# Wiring_Harness_Validator_MX150L_Rev1.net
KiCad netlist of a schematic drawn in EAGLE
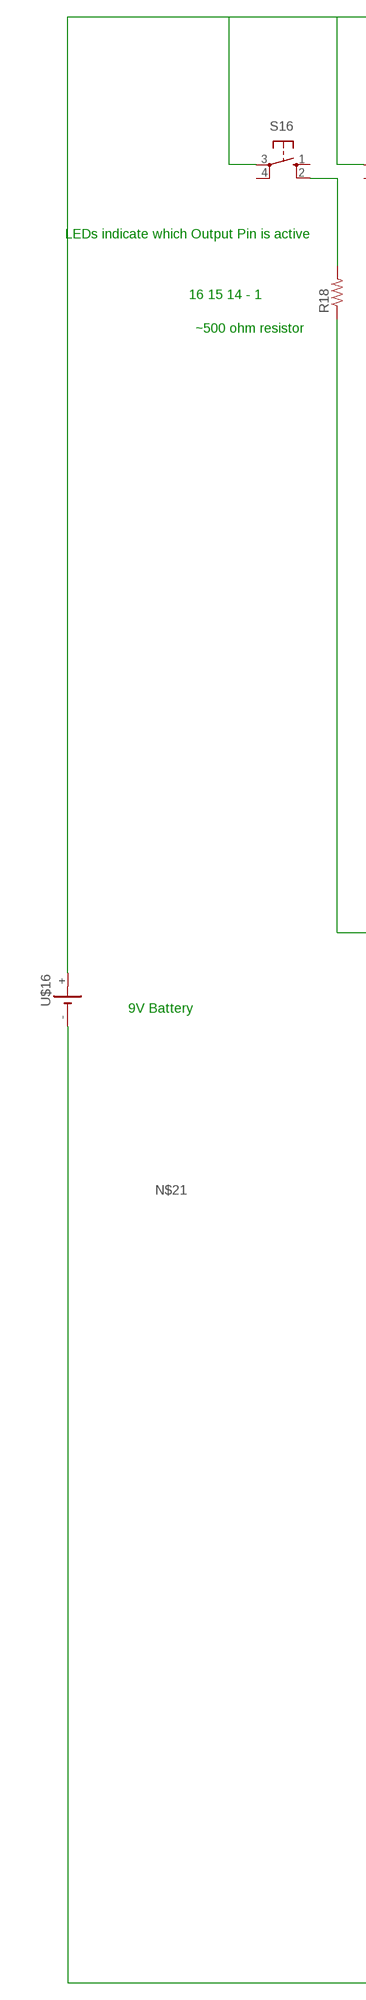
[diagram p0: schematic, sheet 1, part 1 of 2]
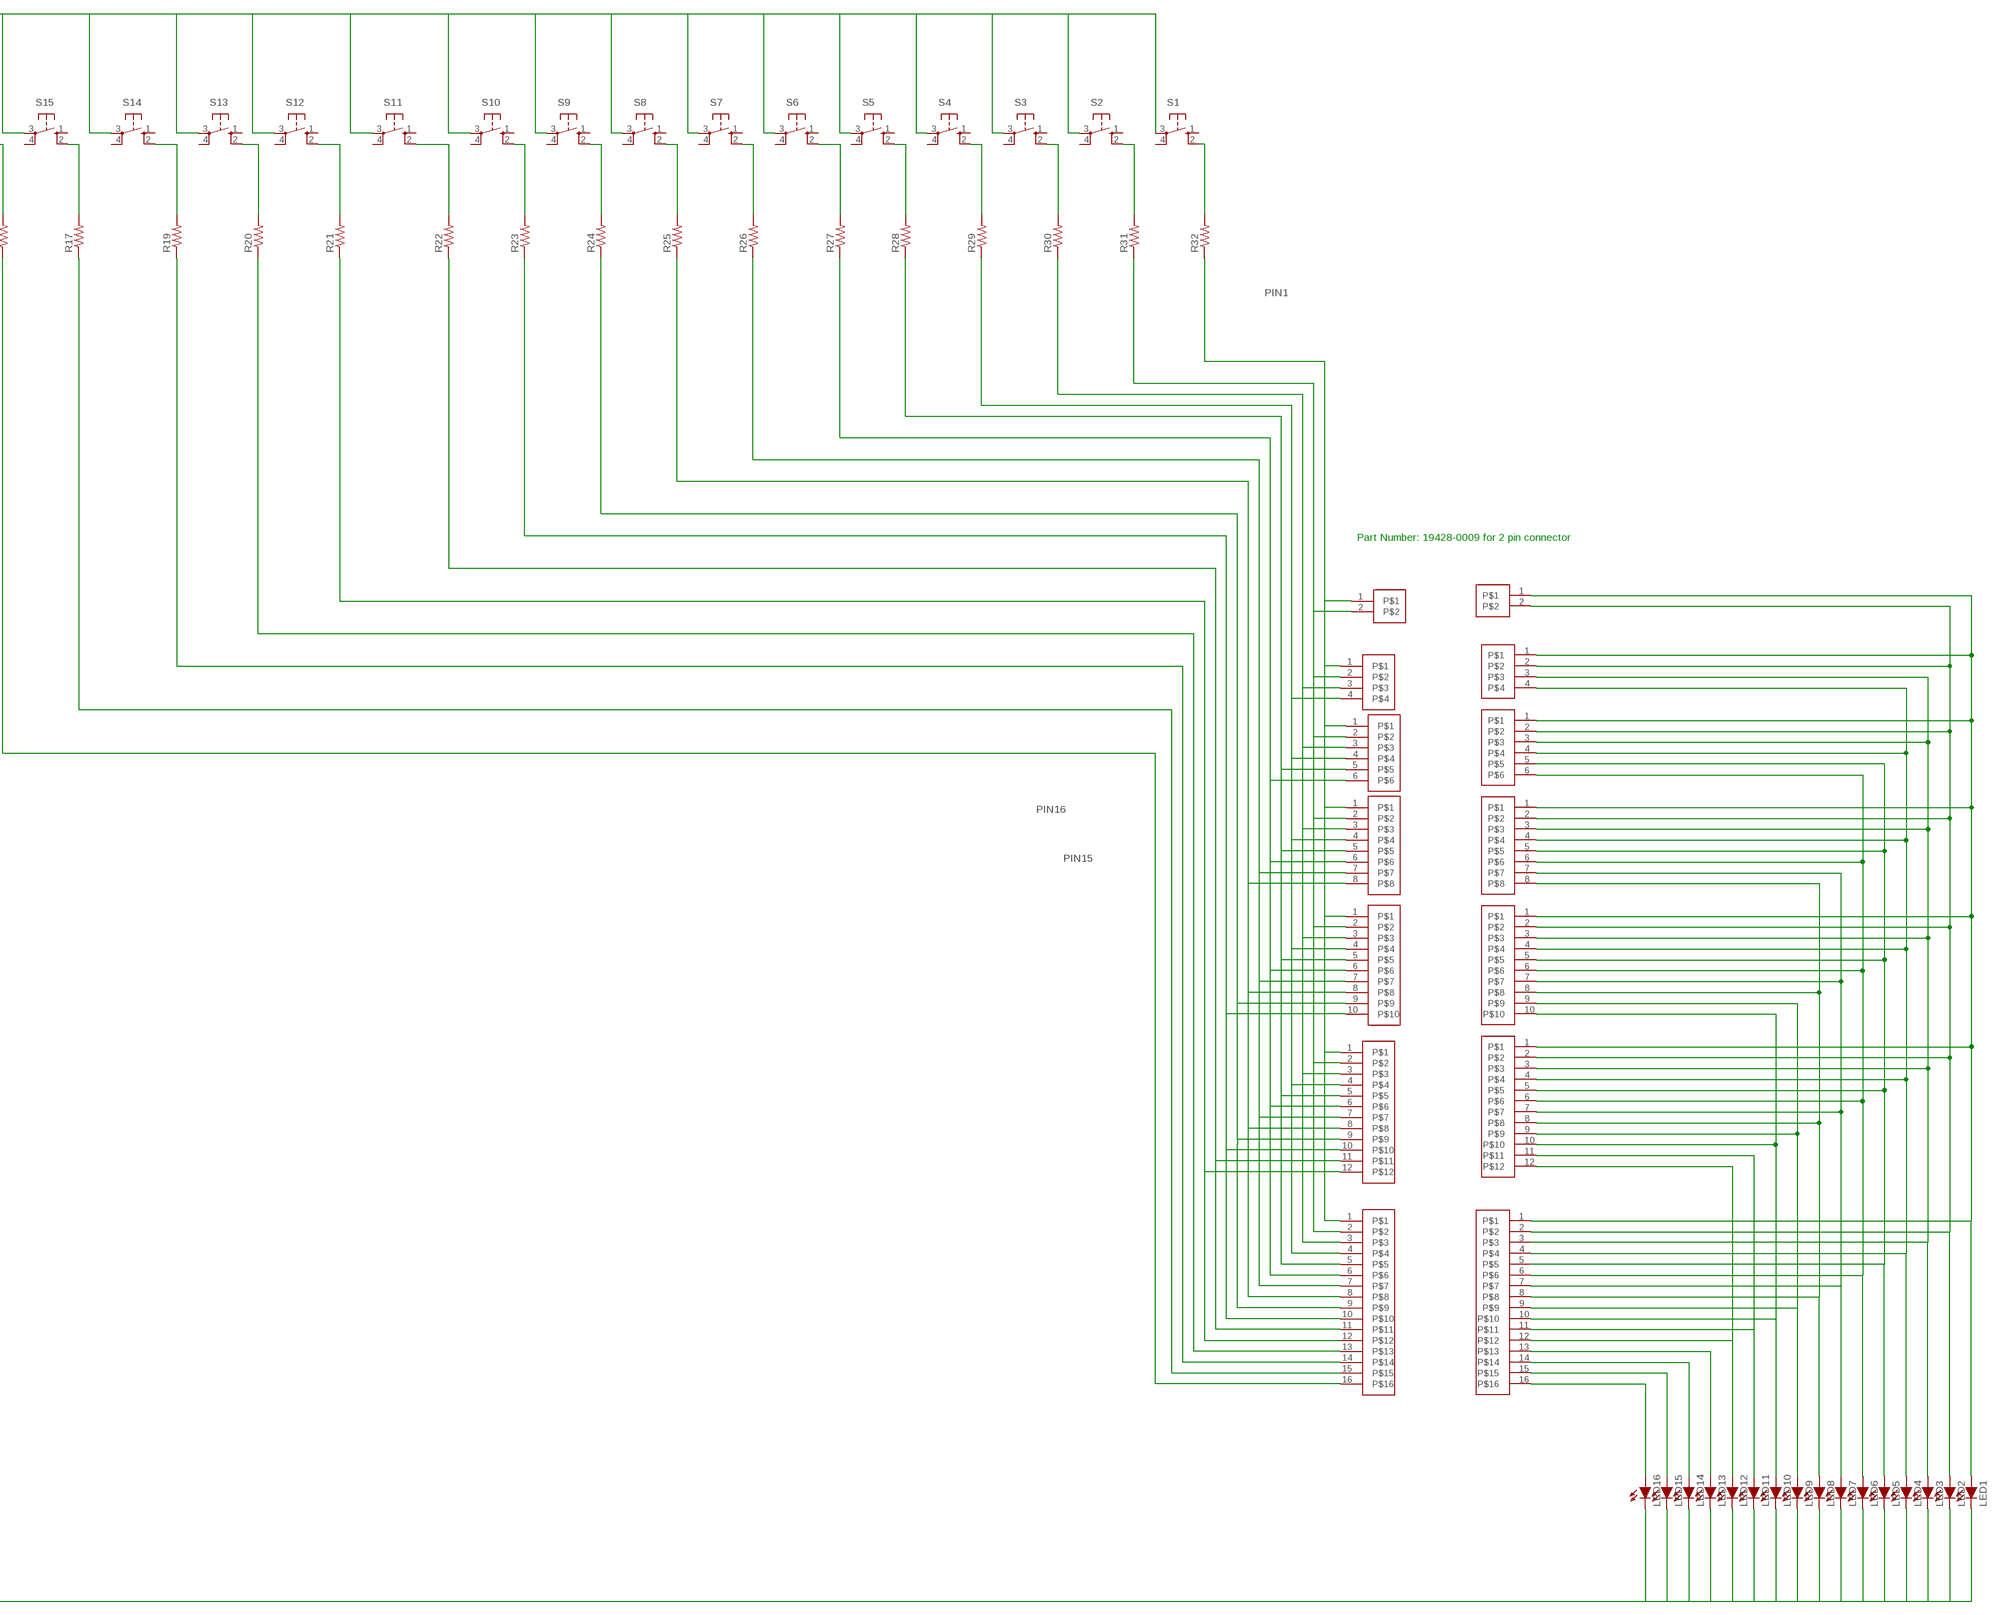
[diagram p1: schematic, sheet 1, part 2 of 2]

(export (version "E")
  (design (tool "Eeschema 10.0.6"))
  (components
    (comp (ref "LED1")
      (value "LED-5MM")
      (footprint "eagle-import:LED-5MM")
      (libsource (lib "eagle-import") (part "LED-5MM"))
    )
    (comp (ref "LED2")
      (value "LED-5MM")
      (footprint "eagle-import:LED-5MM")
      (libsource (lib "eagle-import") (part "LED-5MM"))
    )
    (comp (ref "LED3")
      (value "LED-5MM")
      (footprint "eagle-import:LED-5MM")
      (libsource (lib "eagle-import") (part "LED-5MM"))
    )
    (comp (ref "LED4")
      (value "LED-5MM")
      (footprint "eagle-import:LED-5MM")
      (libsource (lib "eagle-import") (part "LED-5MM"))
    )
    (comp (ref "LED5")
      (value "LED-5MM")
      (footprint "eagle-import:LED-5MM")
      (libsource (lib "eagle-import") (part "LED-5MM"))
    )
    (comp (ref "LED6")
      (value "LED-5MM")
      (footprint "eagle-import:LED-5MM")
      (libsource (lib "eagle-import") (part "LED-5MM"))
    )
    (comp (ref "LED7")
      (value "LED-5MM")
      (footprint "eagle-import:LED-5MM")
      (libsource (lib "eagle-import") (part "LED-5MM"))
    )
    (comp (ref "LED8")
      (value "LED-5MM")
      (footprint "eagle-import:LED-5MM")
      (libsource (lib "eagle-import") (part "LED-5MM"))
    )
    (comp (ref "LED9")
      (value "LED-5MM")
      (footprint "eagle-import:LED-5MM")
      (libsource (lib "eagle-import") (part "LED-5MM"))
    )
    (comp (ref "LED10")
      (value "LED-5MM")
      (footprint "eagle-import:LED-5MM")
      (libsource (lib "eagle-import") (part "LED-5MM"))
    )
    (comp (ref "LED11")
      (value "LED-5MM")
      (footprint "eagle-import:LED-5MM")
      (libsource (lib "eagle-import") (part "LED-5MM"))
    )
    (comp (ref "LED12")
      (value "LED-5MM")
      (footprint "eagle-import:LED-5MM")
      (libsource (lib "eagle-import") (part "LED-5MM"))
    )
    (comp (ref "LED13")
      (value "LED-5MM")
      (footprint "eagle-import:LED-5MM")
      (libsource (lib "eagle-import") (part "LED-5MM"))
    )
    (comp (ref "LED14")
      (value "LED-5MM")
      (footprint "eagle-import:LED-5MM")
      (libsource (lib "eagle-import") (part "LED-5MM"))
    )
    (comp (ref "LED15")
      (value "LED-5MM")
      (footprint "eagle-import:LED-5MM")
      (libsource (lib "eagle-import") (part "LED-5MM"))
    )
    (comp (ref "LED16")
      (value "LED-5MM")
      (footprint "eagle-import:LED-5MM")
      (libsource (lib "eagle-import") (part "LED-5MM"))
    )
    (comp (ref "R17")
      (value "RESISTORPTH-1/2W")
      (footprint "eagle-import:AXIAL-0.5")
      (libsource (lib "eagle-import") (part "RESISTORPTH-1/2W"))
    )
    (comp (ref "R18")
      (value "RESISTORPTH-1/2W")
      (footprint "eagle-import:AXIAL-0.5")
      (libsource (lib "eagle-import") (part "RESISTORPTH-1/2W"))
    )
    (comp (ref "R19")
      (value "RESISTORPTH-1/2W")
      (footprint "eagle-import:AXIAL-0.5")
      (libsource (lib "eagle-import") (part "RESISTORPTH-1/2W"))
    )
    (comp (ref "R20")
      (value "RESISTORPTH-1/2W")
      (footprint "eagle-import:AXIAL-0.5")
      (libsource (lib "eagle-import") (part "RESISTORPTH-1/2W"))
    )
    (comp (ref "R21")
      (value "RESISTORPTH-1/2W")
      (footprint "eagle-import:AXIAL-0.5")
      (libsource (lib "eagle-import") (part "RESISTORPTH-1/2W"))
    )
    (comp (ref "R22")
      (value "RESISTORPTH-1/2W")
      (footprint "eagle-import:AXIAL-0.5")
      (libsource (lib "eagle-import") (part "RESISTORPTH-1/2W"))
    )
    (comp (ref "R23")
      (value "RESISTORPTH-1/2W")
      (footprint "eagle-import:AXIAL-0.5")
      (libsource (lib "eagle-import") (part "RESISTORPTH-1/2W"))
    )
    (comp (ref "R24")
      (value "RESISTORPTH-1/2W")
      (footprint "eagle-import:AXIAL-0.5")
      (libsource (lib "eagle-import") (part "RESISTORPTH-1/2W"))
    )
    (comp (ref "R25")
      (value "RESISTORPTH-1/2W")
      (footprint "eagle-import:AXIAL-0.5")
      (libsource (lib "eagle-import") (part "RESISTORPTH-1/2W"))
    )
    (comp (ref "R26")
      (value "RESISTORPTH-1/2W")
      (footprint "eagle-import:AXIAL-0.5")
      (libsource (lib "eagle-import") (part "RESISTORPTH-1/2W"))
    )
    (comp (ref "R27")
      (value "RESISTORPTH-1/2W")
      (footprint "eagle-import:AXIAL-0.5")
      (libsource (lib "eagle-import") (part "RESISTORPTH-1/2W"))
    )
    (comp (ref "R28")
      (value "RESISTORPTH-1/2W")
      (footprint "eagle-import:AXIAL-0.5")
      (libsource (lib "eagle-import") (part "RESISTORPTH-1/2W"))
    )
    (comp (ref "R29")
      (value "RESISTORPTH-1/2W")
      (footprint "eagle-import:AXIAL-0.5")
      (libsource (lib "eagle-import") (part "RESISTORPTH-1/2W"))
    )
    (comp (ref "R30")
      (value "RESISTORPTH-1/2W")
      (footprint "eagle-import:AXIAL-0.5")
      (libsource (lib "eagle-import") (part "RESISTORPTH-1/2W"))
    )
    (comp (ref "R31")
      (value "RESISTORPTH-1/2W")
      (footprint "eagle-import:AXIAL-0.5")
      (libsource (lib "eagle-import") (part "RESISTORPTH-1/2W"))
    )
    (comp (ref "R32")
      (value "RESISTORPTH-1/2W")
      (footprint "eagle-import:AXIAL-0.5")
      (libsource (lib "eagle-import") (part "RESISTORPTH-1/2W"))
    )
    (comp (ref "S1")
      (value "BTN_10-XX")
      (footprint "eagle-import:B3F-10XX")
      (fields (field (name "MPN") "B3F-1000"))
      (libsource (lib "eagle-import") (part "BTN_10-XX"))
    )
    (comp (ref "S2")
      (value "BTN_10-XX")
      (footprint "eagle-import:B3F-10XX")
      (fields (field (name "MPN") "B3F-1000"))
      (libsource (lib "eagle-import") (part "BTN_10-XX"))
    )
    (comp (ref "S3")
      (value "BTN_10-XX")
      (footprint "eagle-import:B3F-10XX")
      (fields (field (name "MPN") "B3F-1000"))
      (libsource (lib "eagle-import") (part "BTN_10-XX"))
    )
    (comp (ref "S4")
      (value "BTN_10-XX")
      (footprint "eagle-import:B3F-10XX")
      (fields (field (name "MPN") "B3F-1000"))
      (libsource (lib "eagle-import") (part "BTN_10-XX"))
    )
    (comp (ref "S5")
      (value "BTN_10-XX")
      (footprint "eagle-import:B3F-10XX")
      (fields (field (name "MPN") "B3F-1000"))
      (libsource (lib "eagle-import") (part "BTN_10-XX"))
    )
    (comp (ref "S6")
      (value "BTN_10-XX")
      (footprint "eagle-import:B3F-10XX")
      (fields (field (name "MPN") "B3F-1000"))
      (libsource (lib "eagle-import") (part "BTN_10-XX"))
    )
    (comp (ref "S7")
      (value "BTN_10-XX")
      (footprint "eagle-import:B3F-10XX")
      (fields (field (name "MPN") "B3F-1000"))
      (libsource (lib "eagle-import") (part "BTN_10-XX"))
    )
    (comp (ref "S8")
      (value "BTN_10-XX")
      (footprint "eagle-import:B3F-10XX")
      (fields (field (name "MPN") "B3F-1000"))
      (libsource (lib "eagle-import") (part "BTN_10-XX"))
    )
    (comp (ref "S9")
      (value "BTN_10-XX")
      (footprint "eagle-import:B3F-10XX")
      (fields (field (name "MPN") "B3F-1000"))
      (libsource (lib "eagle-import") (part "BTN_10-XX"))
    )
    (comp (ref "S10")
      (value "BTN_10-XX")
      (footprint "eagle-import:B3F-10XX")
      (fields (field (name "MPN") "B3F-1000"))
      (libsource (lib "eagle-import") (part "BTN_10-XX"))
    )
    (comp (ref "S11")
      (value "BTN_10-XX")
      (footprint "eagle-import:B3F-10XX")
      (fields (field (name "MPN") "B3F-1000"))
      (libsource (lib "eagle-import") (part "BTN_10-XX"))
    )
    (comp (ref "S12")
      (value "BTN_10-XX")
      (footprint "eagle-import:B3F-10XX")
      (fields (field (name "MPN") "B3F-1000"))
      (libsource (lib "eagle-import") (part "BTN_10-XX"))
    )
    (comp (ref "S13")
      (value "BTN_10-XX")
      (footprint "eagle-import:B3F-10XX")
      (fields (field (name "MPN") "B3F-1000"))
      (libsource (lib "eagle-import") (part "BTN_10-XX"))
    )
    (comp (ref "S14")
      (value "BTN_10-XX")
      (footprint "eagle-import:B3F-10XX")
      (fields (field (name "MPN") "B3F-1000"))
      (libsource (lib "eagle-import") (part "BTN_10-XX"))
    )
    (comp (ref "S15")
      (value "BTN_10-XX")
      (footprint "eagle-import:B3F-10XX")
      (fields (field (name "MPN") "B3F-1000"))
      (libsource (lib "eagle-import") (part "BTN_10-XX"))
    )
    (comp (ref "S16")
      (value "BTN_10-XX")
      (footprint "eagle-import:B3F-10XX")
      (fields (field (name "MPN") "B3F-1000"))
      (libsource (lib "eagle-import") (part "BTN_10-XX"))
    )
    (comp (ref "U$1")
      (value "MX150L-4PINS")
      (footprint "eagle-import:MX150L_VERTICAL-4")
      (libsource (lib "eagle-import") (part "MX150L-4PINS"))
    )
    (comp (ref "U$2")
      (value "MX150L-6PINS")
      (footprint "eagle-import:MX150L_VERTICAL-6")
      (libsource (lib "eagle-import") (part "MX150L-6PINS"))
    )
    (comp (ref "U$3")
      (value "MX150L-2PINS")
      (footprint "eagle-import:MX150L_VERTICAL-2")
      (libsource (lib "eagle-import") (part "MX150L-2PINS"))
    )
    (comp (ref "U$4")
      (value "MX150L-8PINS")
      (footprint "eagle-import:MX150L_VERTICAL-8")
      (libsource (lib "eagle-import") (part "MX150L-8PINS"))
    )
    (comp (ref "U$5")
      (value "MX150L-10PINS")
      (footprint "eagle-import:MX150L_VERTICAL-10")
      (libsource (lib "eagle-import") (part "MX150L-10PINS"))
    )
    (comp (ref "U$6")
      (value "MX150L-12PINS")
      (footprint "eagle-import:MX150L_VERTICAL-12")
      (libsource (lib "eagle-import") (part "MX150L-12PINS"))
    )
    (comp (ref "U$7")
      (value "MX150L-16PINS")
      (footprint "eagle-import:MX150L-VERTICAL-16")
      (libsource (lib "eagle-import") (part "MX150L-16PINS"))
    )
    (comp (ref "U$8")
      (value "MX150L-16PINS")
      (footprint "eagle-import:MX150L-VERTICAL-16")
      (libsource (lib "eagle-import") (part "MX150L-16PINS"))
    )
    (comp (ref "U$9")
      (value "MX150L-12PINS")
      (footprint "eagle-import:MX150L_VERTICAL-12")
      (libsource (lib "eagle-import") (part "MX150L-12PINS"))
    )
    (comp (ref "U$10")
      (value "MX150L-10PINS")
      (footprint "eagle-import:MX150L_VERTICAL-10")
      (libsource (lib "eagle-import") (part "MX150L-10PINS"))
    )
    (comp (ref "U$11")
      (value "MX150L-8PINS")
      (footprint "eagle-import:MX150L_VERTICAL-8")
      (libsource (lib "eagle-import") (part "MX150L-8PINS"))
    )
    (comp (ref "U$12")
      (value "MX150L-6PINS")
      (footprint "eagle-import:MX150L_VERTICAL-6")
      (libsource (lib "eagle-import") (part "MX150L-6PINS"))
    )
    (comp (ref "U$13")
      (value "MX150L-4PINS")
      (footprint "eagle-import:MX150L_VERTICAL-4")
      (libsource (lib "eagle-import") (part "MX150L-4PINS"))
    )
    (comp (ref "U$14")
      (value "MX150L-2PINS")
      (footprint "eagle-import:MX150L_VERTICAL-2")
      (libsource (lib "eagle-import") (part "MX150L-2PINS"))
    )
    (comp (ref "U$16")
      (value "1291-79")
      (footprint "eagle-import:1291-79")
      (libsource (lib "eagle-import") (part "1291-79"))
    )
  )
  (nets
    (net (code "1") (name "/N$21") (class "Default")
      (node (ref "LED1") (pin "K") (pinfunction "C_K") (pintype "passive"))
      (node (ref "LED10") (pin "K") (pinfunction "C_K") (pintype "passive"))
      (node (ref "LED11") (pin "K") (pinfunction "C_K") (pintype "passive"))
      (node (ref "LED12") (pin "K") (pinfunction "C_K") (pintype "passive"))
      (node (ref "LED13") (pin "K") (pinfunction "C_K") (pintype "passive"))
      (node (ref "LED14") (pin "K") (pinfunction "C_K") (pintype "passive"))
      (node (ref "LED15") (pin "K") (pinfunction "C_K") (pintype "passive"))
      (node (ref "LED16") (pin "K") (pinfunction "C_K") (pintype "passive"))
      (node (ref "LED2") (pin "K") (pinfunction "C_K") (pintype "passive"))
      (node (ref "LED3") (pin "K") (pinfunction "C_K") (pintype "passive"))
      (node (ref "LED4") (pin "K") (pinfunction "C_K") (pintype "passive"))
      (node (ref "LED5") (pin "K") (pinfunction "C_K") (pintype "passive"))
      (node (ref "LED6") (pin "K") (pinfunction "C_K") (pintype "passive"))
      (node (ref "LED7") (pin "K") (pinfunction "C_K") (pintype "passive"))
      (node (ref "LED8") (pin "K") (pinfunction "C_K") (pintype "passive"))
      (node (ref "LED9") (pin "K") (pinfunction "C_K") (pintype "passive"))
      (node (ref "U$16") (pin "-") (pinfunction "-_-") (pintype "passive"))
    )
    (net (code "2") (name "/PIN1") (class "Default")
      (node (ref "R32") (pin "P$1") (pinfunction "1_P$1") (pintype "passive"))
      (node (ref "U$1") (pin "1") (pinfunction "P$1_1") (pintype "bidirectional"))
      (node (ref "U$2") (pin "1") (pinfunction "P$1_1") (pintype "bidirectional"))
      (node (ref "U$3") (pin "1") (pinfunction "P$1_1") (pintype "bidirectional"))
      (node (ref "U$4") (pin "1") (pinfunction "P$1_1") (pintype "bidirectional"))
      (node (ref "U$5") (pin "1") (pinfunction "P$1_1") (pintype "bidirectional"))
      (node (ref "U$6") (pin "1") (pinfunction "P$1_1") (pintype "bidirectional"))
      (node (ref "U$7") (pin "1") (pinfunction "P$1_1") (pintype "bidirectional"))
    )
    (net (code "3") (name "/PIN15") (class "Default")
      (node (ref "R17") (pin "P$1") (pinfunction "1_P$1") (pintype "passive"))
      (node (ref "U$7") (pin "15") (pinfunction "P$15_15") (pintype "bidirectional"))
    )
    (net (code "4") (name "/PIN16") (class "Default")
      (node (ref "R18") (pin "P$1") (pinfunction "1_P$1") (pintype "passive"))
      (node (ref "U$7") (pin "16") (pinfunction "P$16_16") (pintype "bidirectional"))
    )
    (net (code "5") (name "Net-(R17-2)") (class "Default")
      (node (ref "R17") (pin "P$2") (pinfunction "2_P$2") (pintype "passive"))
      (node (ref "S15") (pin "2") (pinfunction "S1_2") (pintype "passive"))
    )
    (net (code "6") (name "Net-(R18-2)") (class "Default")
      (node (ref "R18") (pin "P$2") (pinfunction "2_P$2") (pintype "passive"))
      (node (ref "S16") (pin "2") (pinfunction "S1_2") (pintype "passive"))
    )
    (net (code "7") (name "Net-(R19-1)") (class "Default")
      (node (ref "R19") (pin "P$1") (pinfunction "1_P$1") (pintype "passive"))
      (node (ref "U$7") (pin "14") (pinfunction "P$14_14") (pintype "bidirectional"))
    )
    (net (code "8") (name "Net-(R19-2)") (class "Default")
      (node (ref "R19") (pin "P$2") (pinfunction "2_P$2") (pintype "passive"))
      (node (ref "S14") (pin "2") (pinfunction "S1_2") (pintype "passive"))
    )
    (net (code "9") (name "Net-(R20-1)") (class "Default")
      (node (ref "R20") (pin "P$1") (pinfunction "1_P$1") (pintype "passive"))
      (node (ref "U$7") (pin "13") (pinfunction "P$13_13") (pintype "bidirectional"))
    )
    (net (code "10") (name "Net-(R20-2)") (class "Default")
      (node (ref "R20") (pin "P$2") (pinfunction "2_P$2") (pintype "passive"))
      (node (ref "S13") (pin "2") (pinfunction "S1_2") (pintype "passive"))
    )
    (net (code "11") (name "Net-(R21-1)") (class "Default")
      (node (ref "R21") (pin "P$1") (pinfunction "1_P$1") (pintype "passive"))
      (node (ref "U$6") (pin "12") (pinfunction "P$12_12") (pintype "bidirectional"))
      (node (ref "U$7") (pin "12") (pinfunction "P$12_12") (pintype "bidirectional"))
    )
    (net (code "12") (name "Net-(R21-2)") (class "Default")
      (node (ref "R21") (pin "P$2") (pinfunction "2_P$2") (pintype "passive"))
      (node (ref "S12") (pin "2") (pinfunction "S1_2") (pintype "passive"))
    )
    (net (code "13") (name "Net-(R22-1)") (class "Default")
      (node (ref "R22") (pin "P$1") (pinfunction "1_P$1") (pintype "passive"))
      (node (ref "U$6") (pin "11") (pinfunction "P$11_11") (pintype "bidirectional"))
      (node (ref "U$7") (pin "11") (pinfunction "P$11_11") (pintype "bidirectional"))
    )
    (net (code "14") (name "Net-(R22-2)") (class "Default")
      (node (ref "R22") (pin "P$2") (pinfunction "2_P$2") (pintype "passive"))
      (node (ref "S11") (pin "2") (pinfunction "S1_2") (pintype "passive"))
    )
    (net (code "15") (name "Net-(R23-1)") (class "Default")
      (node (ref "R23") (pin "P$1") (pinfunction "1_P$1") (pintype "passive"))
      (node (ref "U$5") (pin "10") (pinfunction "P$10_10") (pintype "bidirectional"))
      (node (ref "U$6") (pin "10") (pinfunction "P$10_10") (pintype "bidirectional"))
      (node (ref "U$7") (pin "10") (pinfunction "P$10_10") (pintype "bidirectional"))
    )
    (net (code "16") (name "Net-(R23-2)") (class "Default")
      (node (ref "R23") (pin "P$2") (pinfunction "2_P$2") (pintype "passive"))
      (node (ref "S10") (pin "2") (pinfunction "S1_2") (pintype "passive"))
    )
    (net (code "17") (name "Net-(R24-1)") (class "Default")
      (node (ref "R24") (pin "P$1") (pinfunction "1_P$1") (pintype "passive"))
      (node (ref "U$5") (pin "9") (pinfunction "P$9_9") (pintype "bidirectional"))
      (node (ref "U$6") (pin "9") (pinfunction "P$9_9") (pintype "bidirectional"))
      (node (ref "U$7") (pin "9") (pinfunction "P$9_9") (pintype "bidirectional"))
    )
    (net (code "18") (name "Net-(R24-2)") (class "Default")
      (node (ref "R24") (pin "P$2") (pinfunction "2_P$2") (pintype "passive"))
      (node (ref "S9") (pin "2") (pinfunction "S1_2") (pintype "passive"))
    )
    (net (code "19") (name "Net-(R25-1)") (class "Default")
      (node (ref "R25") (pin "P$1") (pinfunction "1_P$1") (pintype "passive"))
      (node (ref "U$4") (pin "8") (pinfunction "P$8_8") (pintype "bidirectional"))
      (node (ref "U$5") (pin "8") (pinfunction "P$8_8") (pintype "bidirectional"))
      (node (ref "U$6") (pin "8") (pinfunction "P$8_8") (pintype "bidirectional"))
      (node (ref "U$7") (pin "8") (pinfunction "P$8_8") (pintype "bidirectional"))
    )
    (net (code "20") (name "Net-(R25-2)") (class "Default")
      (node (ref "R25") (pin "P$2") (pinfunction "2_P$2") (pintype "passive"))
      (node (ref "S8") (pin "2") (pinfunction "S1_2") (pintype "passive"))
    )
    (net (code "21") (name "Net-(R26-1)") (class "Default")
      (node (ref "R26") (pin "P$1") (pinfunction "1_P$1") (pintype "passive"))
      (node (ref "U$4") (pin "7") (pinfunction "P$7_7") (pintype "bidirectional"))
      (node (ref "U$5") (pin "7") (pinfunction "P$7_7") (pintype "bidirectional"))
      (node (ref "U$6") (pin "7") (pinfunction "P$7_7") (pintype "bidirectional"))
      (node (ref "U$7") (pin "7") (pinfunction "P$7_7") (pintype "bidirectional"))
    )
    (net (code "22") (name "Net-(R26-2)") (class "Default")
      (node (ref "R26") (pin "P$2") (pinfunction "2_P$2") (pintype "passive"))
      (node (ref "S7") (pin "2") (pinfunction "S1_2") (pintype "passive"))
    )
    (net (code "23") (name "Net-(R27-1)") (class "Default")
      (node (ref "R27") (pin "P$1") (pinfunction "1_P$1") (pintype "passive"))
      (node (ref "U$2") (pin "6") (pinfunction "P$6_6") (pintype "bidirectional"))
      (node (ref "U$4") (pin "6") (pinfunction "P$6_6") (pintype "bidirectional"))
      (node (ref "U$5") (pin "6") (pinfunction "P$6_6") (pintype "bidirectional"))
      (node (ref "U$6") (pin "6") (pinfunction "P$6_6") (pintype "bidirectional"))
      (node (ref "U$7") (pin "6") (pinfunction "P$6_6") (pintype "bidirectional"))
    )
    (net (code "24") (name "Net-(R27-2)") (class "Default")
      (node (ref "R27") (pin "P$2") (pinfunction "2_P$2") (pintype "passive"))
      (node (ref "S6") (pin "2") (pinfunction "S1_2") (pintype "passive"))
    )
    (net (code "25") (name "Net-(R28-1)") (class "Default")
      (node (ref "R28") (pin "P$1") (pinfunction "1_P$1") (pintype "passive"))
      (node (ref "U$2") (pin "5") (pinfunction "P$5_5") (pintype "bidirectional"))
      (node (ref "U$4") (pin "5") (pinfunction "P$5_5") (pintype "bidirectional"))
      (node (ref "U$5") (pin "5") (pinfunction "P$5_5") (pintype "bidirectional"))
      (node (ref "U$6") (pin "5") (pinfunction "P$5_5") (pintype "bidirectional"))
      (node (ref "U$7") (pin "5") (pinfunction "P$5_5") (pintype "bidirectional"))
    )
    (net (code "26") (name "Net-(R28-2)") (class "Default")
      (node (ref "R28") (pin "P$2") (pinfunction "2_P$2") (pintype "passive"))
      (node (ref "S5") (pin "2") (pinfunction "S1_2") (pintype "passive"))
    )
    (net (code "27") (name "Net-(R29-1)") (class "Default")
      (node (ref "R29") (pin "P$1") (pinfunction "1_P$1") (pintype "passive"))
      (node (ref "U$1") (pin "4") (pinfunction "P$4_4") (pintype "bidirectional"))
      (node (ref "U$2") (pin "4") (pinfunction "P$4_4") (pintype "bidirectional"))
      (node (ref "U$4") (pin "4") (pinfunction "P$4_4") (pintype "bidirectional"))
      (node (ref "U$5") (pin "4") (pinfunction "P$4_4") (pintype "bidirectional"))
      (node (ref "U$6") (pin "4") (pinfunction "P$4_4") (pintype "bidirectional"))
      (node (ref "U$7") (pin "4") (pinfunction "P$4_4") (pintype "bidirectional"))
    )
    (net (code "28") (name "Net-(R29-2)") (class "Default")
      (node (ref "R29") (pin "P$2") (pinfunction "2_P$2") (pintype "passive"))
      (node (ref "S4") (pin "2") (pinfunction "S1_2") (pintype "passive"))
    )
    (net (code "29") (name "Net-(R30-1)") (class "Default")
      (node (ref "R30") (pin "P$1") (pinfunction "1_P$1") (pintype "passive"))
      (node (ref "U$1") (pin "3") (pinfunction "P$3_3") (pintype "bidirectional"))
      (node (ref "U$2") (pin "3") (pinfunction "P$3_3") (pintype "bidirectional"))
      (node (ref "U$4") (pin "3") (pinfunction "P$3_3") (pintype "bidirectional"))
      (node (ref "U$5") (pin "3") (pinfunction "P$3_3") (pintype "bidirectional"))
      (node (ref "U$6") (pin "3") (pinfunction "P$3_3") (pintype "bidirectional"))
      (node (ref "U$7") (pin "3") (pinfunction "P$3_3") (pintype "bidirectional"))
    )
    (net (code "30") (name "Net-(R30-2)") (class "Default")
      (node (ref "R30") (pin "P$2") (pinfunction "2_P$2") (pintype "passive"))
      (node (ref "S3") (pin "2") (pinfunction "S1_2") (pintype "passive"))
    )
    (net (code "31") (name "Net-(R31-1)") (class "Default")
      (node (ref "R31") (pin "P$1") (pinfunction "1_P$1") (pintype "passive"))
      (node (ref "U$1") (pin "2") (pinfunction "P$2_2") (pintype "bidirectional"))
      (node (ref "U$2") (pin "2") (pinfunction "P$2_2") (pintype "bidirectional"))
      (node (ref "U$3") (pin "2") (pinfunction "P$2_2") (pintype "bidirectional"))
      (node (ref "U$4") (pin "2") (pinfunction "P$2_2") (pintype "bidirectional"))
      (node (ref "U$5") (pin "2") (pinfunction "P$2_2") (pintype "bidirectional"))
      (node (ref "U$6") (pin "2") (pinfunction "P$2_2") (pintype "bidirectional"))
      (node (ref "U$7") (pin "2") (pinfunction "P$2_2") (pintype "bidirectional"))
    )
    (net (code "32") (name "Net-(R31-2)") (class "Default")
      (node (ref "R31") (pin "P$2") (pinfunction "2_P$2") (pintype "passive"))
      (node (ref "S2") (pin "2") (pinfunction "S1_2") (pintype "passive"))
    )
    (net (code "33") (name "Net-(R32-2)") (class "Default")
      (node (ref "R32") (pin "P$2") (pinfunction "2_P$2") (pintype "passive"))
      (node (ref "S1") (pin "2") (pinfunction "S1_2") (pintype "passive"))
    )
    (net (code "34") (name "Net-(S1-P)") (class "Default")
      (node (ref "S1") (pin "3") (pinfunction "P_3") (pintype "passive"))
      (node (ref "S10") (pin "3") (pinfunction "P_3") (pintype "passive"))
      (node (ref "S11") (pin "3") (pinfunction "P_3") (pintype "passive"))
      (node (ref "S12") (pin "3") (pinfunction "P_3") (pintype "passive"))
      (node (ref "S13") (pin "3") (pinfunction "P_3") (pintype "passive"))
      (node (ref "S14") (pin "3") (pinfunction "P_3") (pintype "passive"))
      (node (ref "S15") (pin "3") (pinfunction "P_3") (pintype "passive"))
      (node (ref "S16") (pin "3") (pinfunction "P_3") (pintype "passive"))
      (node (ref "S2") (pin "3") (pinfunction "P_3") (pintype "passive"))
      (node (ref "S3") (pin "3") (pinfunction "P_3") (pintype "passive"))
      (node (ref "S4") (pin "3") (pinfunction "P_3") (pintype "passive"))
      (node (ref "S5") (pin "3") (pinfunction "P_3") (pintype "passive"))
      (node (ref "S6") (pin "3") (pinfunction "P_3") (pintype "passive"))
      (node (ref "S7") (pin "3") (pinfunction "P_3") (pintype "passive"))
      (node (ref "S8") (pin "3") (pinfunction "P_3") (pintype "passive"))
      (node (ref "S9") (pin "3") (pinfunction "P_3") (pintype "passive"))
      (node (ref "U$16") (pin "+") (pinfunction "+_+") (pintype "passive"))
    )
    (net (code "35") (name "Net-(U$8-P$11)") (class "Default")
      (node (ref "LED11") (pin "A") (pinfunction "A_A") (pintype "passive"))
      (node (ref "U$8") (pin "11") (pinfunction "P$11_11") (pintype "bidirectional"))
      (node (ref "U$9") (pin "11") (pinfunction "P$11_11") (pintype "bidirectional"))
    )
    (net (code "36") (name "Net-(U$8-P$12)") (class "Default")
      (node (ref "LED12") (pin "A") (pinfunction "A_A") (pintype "passive"))
      (node (ref "U$8") (pin "12") (pinfunction "P$12_12") (pintype "bidirectional"))
      (node (ref "U$9") (pin "12") (pinfunction "P$12_12") (pintype "bidirectional"))
    )
    (net (code "37") (name "Net-(U$8-P$13)") (class "Default")
      (node (ref "LED13") (pin "A") (pinfunction "A_A") (pintype "passive"))
      (node (ref "U$8") (pin "13") (pinfunction "P$13_13") (pintype "bidirectional"))
    )
    (net (code "38") (name "Net-(U$8-P$14)") (class "Default")
      (node (ref "LED14") (pin "A") (pinfunction "A_A") (pintype "passive"))
      (node (ref "U$8") (pin "14") (pinfunction "P$14_14") (pintype "bidirectional"))
    )
    (net (code "39") (name "Net-(U$8-P$15)") (class "Default")
      (node (ref "LED15") (pin "A") (pinfunction "A_A") (pintype "passive"))
      (node (ref "U$8") (pin "15") (pinfunction "P$15_15") (pintype "bidirectional"))
    )
    (net (code "40") (name "Net-(U$8-P$16)") (class "Default")
      (node (ref "LED16") (pin "A") (pinfunction "A_A") (pintype "passive"))
      (node (ref "U$8") (pin "16") (pinfunction "P$16_16") (pintype "bidirectional"))
    )
    (net (code "41") (name "Net-(U$10-P$1)") (class "Default")
      (node (ref "LED1") (pin "A") (pinfunction "A_A") (pintype "passive"))
      (node (ref "U$10") (pin "1") (pinfunction "P$1_1") (pintype "bidirectional"))
      (node (ref "U$11") (pin "1") (pinfunction "P$1_1") (pintype "bidirectional"))
      (node (ref "U$12") (pin "1") (pinfunction "P$1_1") (pintype "bidirectional"))
      (node (ref "U$13") (pin "1") (pinfunction "P$1_1") (pintype "bidirectional"))
      (node (ref "U$14") (pin "1") (pinfunction "P$1_1") (pintype "bidirectional"))
      (node (ref "U$8") (pin "1") (pinfunction "P$1_1") (pintype "bidirectional"))
      (node (ref "U$9") (pin "1") (pinfunction "P$1_1") (pintype "bidirectional"))
    )
    (net (code "42") (name "Net-(U$10-P$2)") (class "Default")
      (node (ref "LED2") (pin "A") (pinfunction "A_A") (pintype "passive"))
      (node (ref "U$10") (pin "2") (pinfunction "P$2_2") (pintype "bidirectional"))
      (node (ref "U$11") (pin "2") (pinfunction "P$2_2") (pintype "bidirectional"))
      (node (ref "U$12") (pin "2") (pinfunction "P$2_2") (pintype "bidirectional"))
      (node (ref "U$13") (pin "2") (pinfunction "P$2_2") (pintype "bidirectional"))
      (node (ref "U$14") (pin "2") (pinfunction "P$2_2") (pintype "bidirectional"))
      (node (ref "U$8") (pin "2") (pinfunction "P$2_2") (pintype "bidirectional"))
      (node (ref "U$9") (pin "2") (pinfunction "P$2_2") (pintype "bidirectional"))
    )
    (net (code "43") (name "Net-(U$10-P$3)") (class "Default")
      (node (ref "LED3") (pin "A") (pinfunction "A_A") (pintype "passive"))
      (node (ref "U$10") (pin "3") (pinfunction "P$3_3") (pintype "bidirectional"))
      (node (ref "U$11") (pin "3") (pinfunction "P$3_3") (pintype "bidirectional"))
      (node (ref "U$12") (pin "3") (pinfunction "P$3_3") (pintype "bidirectional"))
      (node (ref "U$13") (pin "3") (pinfunction "P$3_3") (pintype "bidirectional"))
      (node (ref "U$8") (pin "3") (pinfunction "P$3_3") (pintype "bidirectional"))
      (node (ref "U$9") (pin "3") (pinfunction "P$3_3") (pintype "bidirectional"))
    )
    (net (code "44") (name "Net-(U$10-P$4)") (class "Default")
      (node (ref "LED4") (pin "A") (pinfunction "A_A") (pintype "passive"))
      (node (ref "U$10") (pin "4") (pinfunction "P$4_4") (pintype "bidirectional"))
      (node (ref "U$11") (pin "4") (pinfunction "P$4_4") (pintype "bidirectional"))
      (node (ref "U$12") (pin "4") (pinfunction "P$4_4") (pintype "bidirectional"))
      (node (ref "U$13") (pin "4") (pinfunction "P$4_4") (pintype "bidirectional"))
      (node (ref "U$8") (pin "4") (pinfunction "P$4_4") (pintype "bidirectional"))
      (node (ref "U$9") (pin "4") (pinfunction "P$4_4") (pintype "bidirectional"))
    )
    (net (code "45") (name "Net-(U$10-P$5)") (class "Default")
      (node (ref "LED5") (pin "A") (pinfunction "A_A") (pintype "passive"))
      (node (ref "U$10") (pin "5") (pinfunction "P$5_5") (pintype "bidirectional"))
      (node (ref "U$11") (pin "5") (pinfunction "P$5_5") (pintype "bidirectional"))
      (node (ref "U$12") (pin "5") (pinfunction "P$5_5") (pintype "bidirectional"))
      (node (ref "U$8") (pin "5") (pinfunction "P$5_5") (pintype "bidirectional"))
      (node (ref "U$9") (pin "5") (pinfunction "P$5_5") (pintype "bidirectional"))
    )
    (net (code "46") (name "Net-(U$10-P$6)") (class "Default")
      (node (ref "LED6") (pin "A") (pinfunction "A_A") (pintype "passive"))
      (node (ref "U$10") (pin "6") (pinfunction "P$6_6") (pintype "bidirectional"))
      (node (ref "U$11") (pin "6") (pinfunction "P$6_6") (pintype "bidirectional"))
      (node (ref "U$12") (pin "6") (pinfunction "P$6_6") (pintype "bidirectional"))
      (node (ref "U$8") (pin "6") (pinfunction "P$6_6") (pintype "bidirectional"))
      (node (ref "U$9") (pin "6") (pinfunction "P$6_6") (pintype "bidirectional"))
    )
    (net (code "47") (name "Net-(U$10-P$7)") (class "Default")
      (node (ref "LED7") (pin "A") (pinfunction "A_A") (pintype "passive"))
      (node (ref "U$10") (pin "7") (pinfunction "P$7_7") (pintype "bidirectional"))
      (node (ref "U$11") (pin "7") (pinfunction "P$7_7") (pintype "bidirectional"))
      (node (ref "U$8") (pin "7") (pinfunction "P$7_7") (pintype "bidirectional"))
      (node (ref "U$9") (pin "7") (pinfunction "P$7_7") (pintype "bidirectional"))
    )
    (net (code "48") (name "Net-(U$10-P$8)") (class "Default")
      (node (ref "LED8") (pin "A") (pinfunction "A_A") (pintype "passive"))
      (node (ref "U$10") (pin "8") (pinfunction "P$8_8") (pintype "bidirectional"))
      (node (ref "U$11") (pin "8") (pinfunction "P$8_8") (pintype "bidirectional"))
      (node (ref "U$8") (pin "8") (pinfunction "P$8_8") (pintype "bidirectional"))
      (node (ref "U$9") (pin "8") (pinfunction "P$8_8") (pintype "bidirectional"))
    )
    (net (code "49") (name "Net-(U$10-P$9)") (class "Default")
      (node (ref "LED9") (pin "A") (pinfunction "A_A") (pintype "passive"))
      (node (ref "U$10") (pin "9") (pinfunction "P$9_9") (pintype "bidirectional"))
      (node (ref "U$8") (pin "9") (pinfunction "P$9_9") (pintype "bidirectional"))
      (node (ref "U$9") (pin "9") (pinfunction "P$9_9") (pintype "bidirectional"))
    )
    (net (code "50") (name "Net-(U$10-P$10)") (class "Default")
      (node (ref "LED10") (pin "A") (pinfunction "A_A") (pintype "passive"))
      (node (ref "U$10") (pin "10") (pinfunction "P$10_10") (pintype "bidirectional"))
      (node (ref "U$8") (pin "10") (pinfunction "P$10_10") (pintype "bidirectional"))
      (node (ref "U$9") (pin "10") (pinfunction "P$10_10") (pintype "bidirectional"))
    )
    (net (code "51") (name "unconnected-(S1-P1-Pad4)") (class "Default")
      (node (ref "S1") (pin "4") (pinfunction "P1_4") (pintype "passive"))
    )
    (net (code "52") (name "unconnected-(S1-S-Pad1)") (class "Default")
      (node (ref "S1") (pin "1") (pinfunction "S_1") (pintype "passive"))
    )
    (net (code "53") (name "unconnected-(S2-P1-Pad4)") (class "Default")
      (node (ref "S2") (pin "4") (pinfunction "P1_4") (pintype "passive"))
    )
    (net (code "54") (name "unconnected-(S2-S-Pad1)") (class "Default")
      (node (ref "S2") (pin "1") (pinfunction "S_1") (pintype "passive"))
    )
    (net (code "55") (name "unconnected-(S3-P1-Pad4)") (class "Default")
      (node (ref "S3") (pin "4") (pinfunction "P1_4") (pintype "passive"))
    )
    (net (code "56") (name "unconnected-(S3-S-Pad1)") (class "Default")
      (node (ref "S3") (pin "1") (pinfunction "S_1") (pintype "passive"))
    )
    (net (code "57") (name "unconnected-(S4-P1-Pad4)") (class "Default")
      (node (ref "S4") (pin "4") (pinfunction "P1_4") (pintype "passive"))
    )
    (net (code "58") (name "unconnected-(S4-S-Pad1)") (class "Default")
      (node (ref "S4") (pin "1") (pinfunction "S_1") (pintype "passive"))
    )
    (net (code "59") (name "unconnected-(S5-P1-Pad4)") (class "Default")
      (node (ref "S5") (pin "4") (pinfunction "P1_4") (pintype "passive"))
    )
    (net (code "60") (name "unconnected-(S5-S-Pad1)") (class "Default")
      (node (ref "S5") (pin "1") (pinfunction "S_1") (pintype "passive"))
    )
    (net (code "61") (name "unconnected-(S6-P1-Pad4)") (class "Default")
      (node (ref "S6") (pin "4") (pinfunction "P1_4") (pintype "passive"))
    )
    (net (code "62") (name "unconnected-(S6-S-Pad1)") (class "Default")
      (node (ref "S6") (pin "1") (pinfunction "S_1") (pintype "passive"))
    )
    (net (code "63") (name "unconnected-(S7-P1-Pad4)") (class "Default")
      (node (ref "S7") (pin "4") (pinfunction "P1_4") (pintype "passive"))
    )
    (net (code "64") (name "unconnected-(S7-S-Pad1)") (class "Default")
      (node (ref "S7") (pin "1") (pinfunction "S_1") (pintype "passive"))
    )
    (net (code "65") (name "unconnected-(S8-P1-Pad4)") (class "Default")
      (node (ref "S8") (pin "4") (pinfunction "P1_4") (pintype "passive"))
    )
    (net (code "66") (name "unconnected-(S8-S-Pad1)") (class "Default")
      (node (ref "S8") (pin "1") (pinfunction "S_1") (pintype "passive"))
    )
    (net (code "67") (name "unconnected-(S9-P1-Pad4)") (class "Default")
      (node (ref "S9") (pin "4") (pinfunction "P1_4") (pintype "passive"))
    )
    (net (code "68") (name "unconnected-(S9-S-Pad1)") (class "Default")
      (node (ref "S9") (pin "1") (pinfunction "S_1") (pintype "passive"))
    )
    (net (code "69") (name "unconnected-(S10-P1-Pad4)") (class "Default")
      (node (ref "S10") (pin "4") (pinfunction "P1_4") (pintype "passive"))
    )
    (net (code "70") (name "unconnected-(S10-S-Pad1)") (class "Default")
      (node (ref "S10") (pin "1") (pinfunction "S_1") (pintype "passive"))
    )
    (net (code "71") (name "unconnected-(S11-P1-Pad4)") (class "Default")
      (node (ref "S11") (pin "4") (pinfunction "P1_4") (pintype "passive"))
    )
    (net (code "72") (name "unconnected-(S11-S-Pad1)") (class "Default")
      (node (ref "S11") (pin "1") (pinfunction "S_1") (pintype "passive"))
    )
    (net (code "73") (name "unconnected-(S12-P1-Pad4)") (class "Default")
      (node (ref "S12") (pin "4") (pinfunction "P1_4") (pintype "passive"))
    )
    (net (code "74") (name "unconnected-(S12-S-Pad1)") (class "Default")
      (node (ref "S12") (pin "1") (pinfunction "S_1") (pintype "passive"))
    )
    (net (code "75") (name "unconnected-(S13-P1-Pad4)") (class "Default")
      (node (ref "S13") (pin "4") (pinfunction "P1_4") (pintype "passive"))
    )
    (net (code "76") (name "unconnected-(S13-S-Pad1)") (class "Default")
      (node (ref "S13") (pin "1") (pinfunction "S_1") (pintype "passive"))
    )
    (net (code "77") (name "unconnected-(S14-P1-Pad4)") (class "Default")
      (node (ref "S14") (pin "4") (pinfunction "P1_4") (pintype "passive"))
    )
    (net (code "78") (name "unconnected-(S14-S-Pad1)") (class "Default")
      (node (ref "S14") (pin "1") (pinfunction "S_1") (pintype "passive"))
    )
    (net (code "79") (name "unconnected-(S15-P1-Pad4)") (class "Default")
      (node (ref "S15") (pin "4") (pinfunction "P1_4") (pintype "passive"))
    )
    (net (code "80") (name "unconnected-(S15-S-Pad1)") (class "Default")
      (node (ref "S15") (pin "1") (pinfunction "S_1") (pintype "passive"))
    )
    (net (code "81") (name "unconnected-(S16-P1-Pad4)") (class "Default")
      (node (ref "S16") (pin "4") (pinfunction "P1_4") (pintype "passive"))
    )
    (net (code "82") (name "unconnected-(S16-S-Pad1)") (class "Default")
      (node (ref "S16") (pin "1") (pinfunction "S_1") (pintype "passive"))
    )
  )
)
